# temp-battery-board.net
KiCad netlist of a schematic drawn in EAGLE
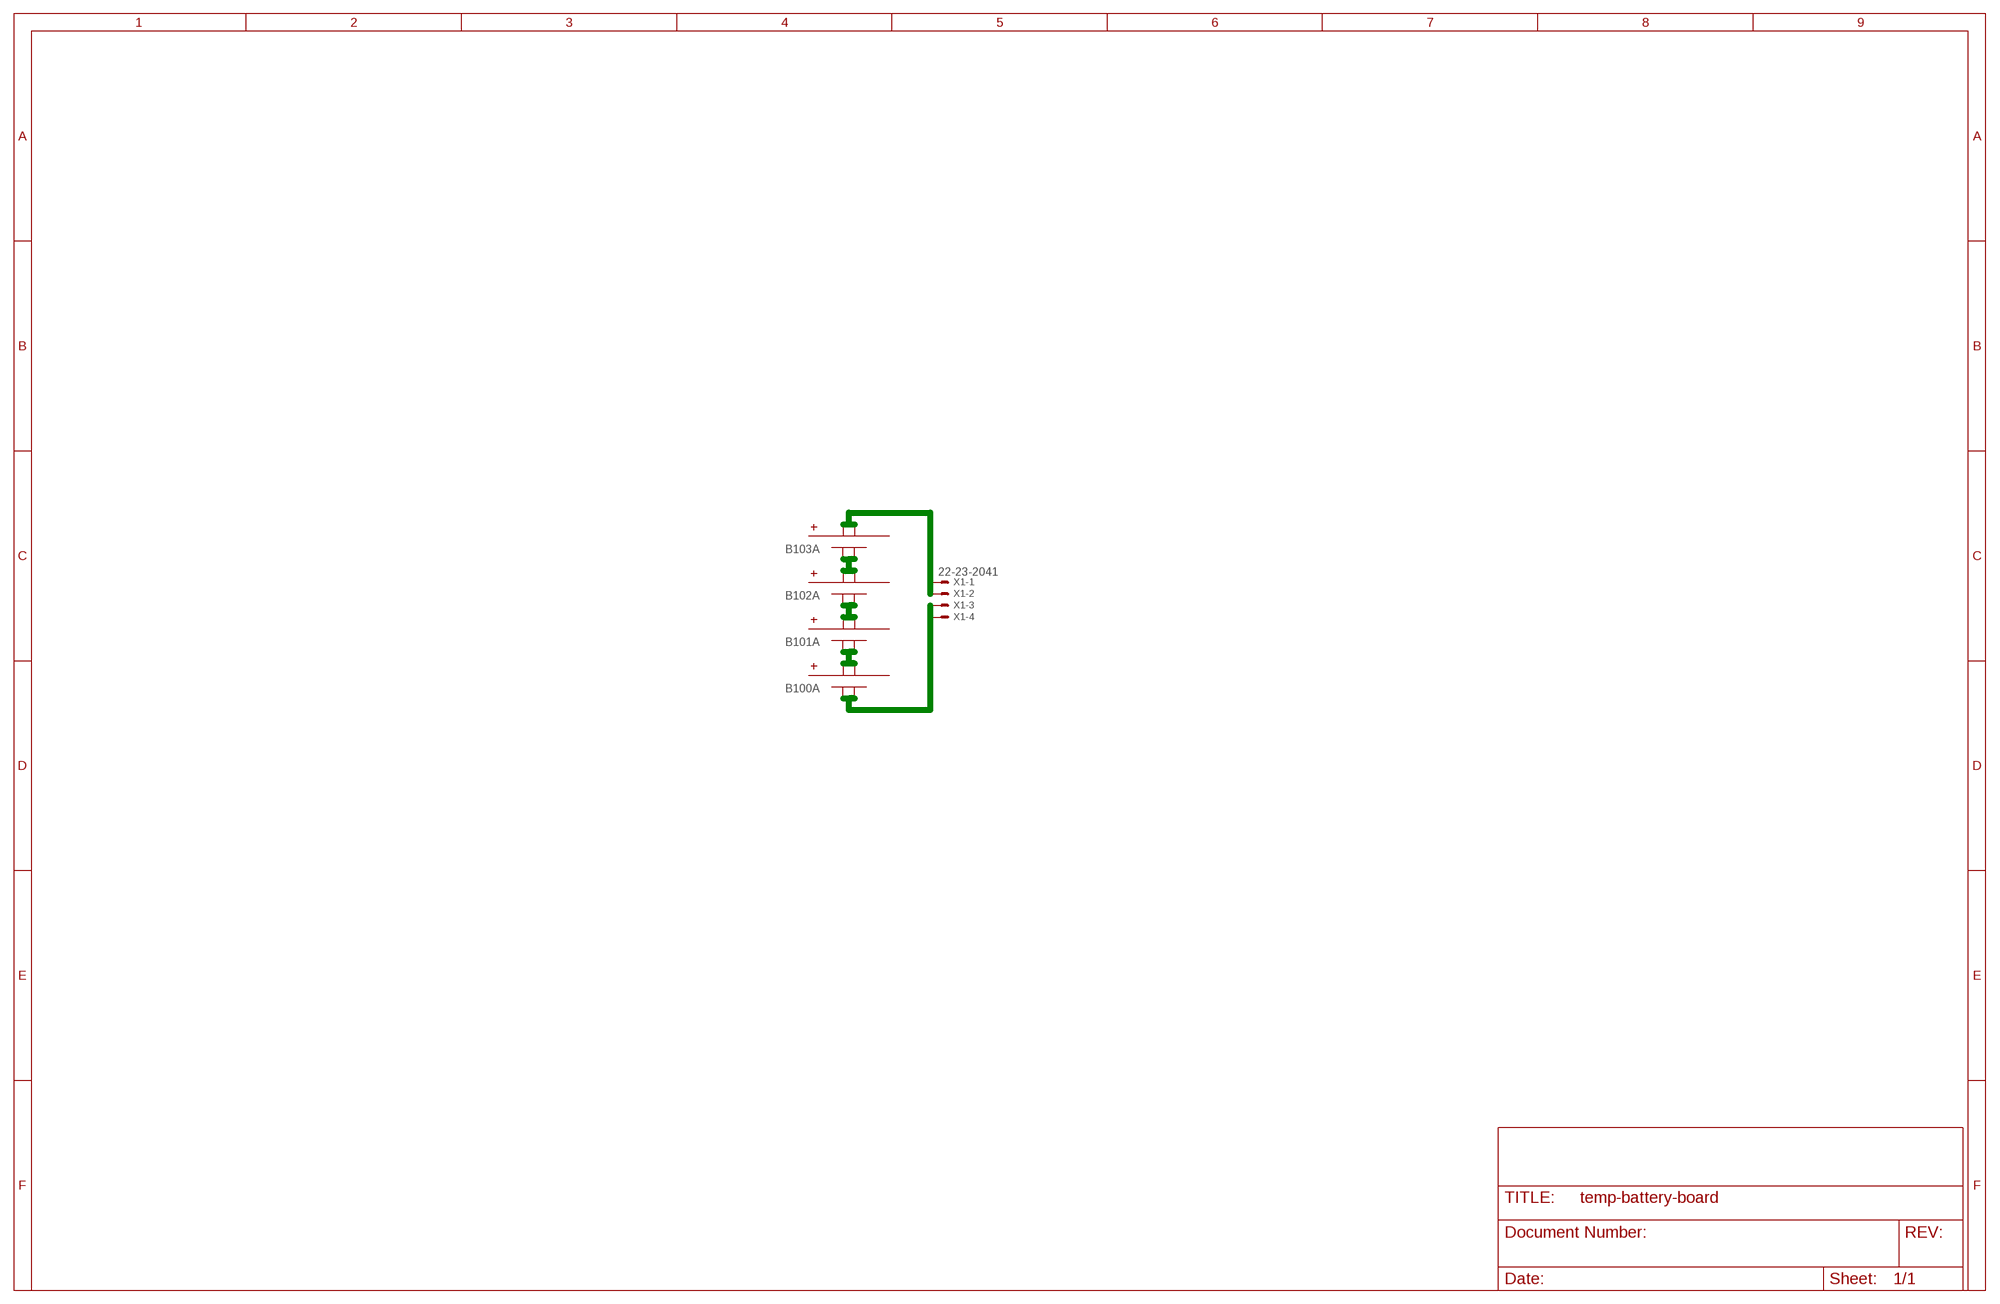
[diagram p0: schematic, sheet 1]

(export (version "E")
  (design (tool "Eeschema 10.0.6"))
  (components
    (comp (ref "B100A")
      (value "LIPO-8AHR")
      (footprint "eagle-import:LIPO-8AHR-PAC")
      (libsource (lib "eagle-import") (part "LIPO-8AHR"))
    )
    (comp (ref "B101A")
      (value "LIPO-8AHR")
      (footprint "eagle-import:LIPO-8AHR-PAC")
      (libsource (lib "eagle-import") (part "LIPO-8AHR"))
    )
    (comp (ref "B102A")
      (value "LIPO-8AHR")
      (footprint "eagle-import:LIPO-8AHR-PAC")
      (libsource (lib "eagle-import") (part "LIPO-8AHR"))
    )
    (comp (ref "B103A")
      (value "LIPO-8AHR")
      (footprint "eagle-import:LIPO-8AHR-PAC")
      (libsource (lib "eagle-import") (part "LIPO-8AHR"))
    )
    (comp (ref "X1")
      (value "22-23-2041")
      (footprint "eagle-import:22-23-2041")
      (libsource (lib "eagle-import") (part "22-23-2041"))
    )
  )
  (nets
    (net (code "1") (name "Net-(B100A-B+-PadB+@1)") (class "Default")
      (node (ref "B100A") (pin "B+@1") (pinfunction "B+_B+@1") (pintype "passive"))
      (node (ref "B100A") (pin "B+@2") (pinfunction "B+_B+@2") (pintype "passive"))
      (node (ref "B101A") (pin "B-@1") (pinfunction "B-_B-@1") (pintype "passive"))
      (node (ref "B101A") (pin "B-@2") (pinfunction "B-_B-@2") (pintype "passive"))
    )
    (net (code "2") (name "Net-(B101A-B+-PadB+@1)") (class "Default")
      (node (ref "B101A") (pin "B+@1") (pinfunction "B+_B+@1") (pintype "passive"))
      (node (ref "B101A") (pin "B+@2") (pinfunction "B+_B+@2") (pintype "passive"))
      (node (ref "B102A") (pin "B-@1") (pinfunction "B-_B-@1") (pintype "passive"))
      (node (ref "B102A") (pin "B-@2") (pinfunction "B-_B-@2") (pintype "passive"))
    )
    (net (code "3") (name "Net-(B102A-B+-PadB+@1)") (class "Default")
      (node (ref "B102A") (pin "B+@1") (pinfunction "B+_B+@1") (pintype "passive"))
      (node (ref "B102A") (pin "B+@2") (pinfunction "B+_B+@2") (pintype "passive"))
      (node (ref "B103A") (pin "B-@1") (pinfunction "B-_B-@1") (pintype "passive"))
      (node (ref "B103A") (pin "B-@2") (pinfunction "B-_B-@2") (pintype "passive"))
    )
    (net (code "4") (name "Net-(X1A-S)") (class "Default")
      (node (ref "B103A") (pin "B+@1") (pinfunction "B+_B+@1") (pintype "passive"))
      (node (ref "B103A") (pin "B+@2") (pinfunction "B+_B+@2") (pintype "passive"))
      (node (ref "X1") (pin "1") (pinfunction "S_1") (pintype "passive"))
      (node (ref "X1") (pin "2") (pinfunction "S_2") (pintype "passive"))
    )
    (net (code "5") (name "Net-(X1C-S)") (class "Default")
      (node (ref "B100A") (pin "B-@1") (pinfunction "B-_B-@1") (pintype "passive"))
      (node (ref "B100A") (pin "B-@2") (pinfunction "B-_B-@2") (pintype "passive"))
      (node (ref "X1") (pin "3") (pinfunction "S_3") (pintype "passive"))
      (node (ref "X1") (pin "4") (pinfunction "S_4") (pintype "passive"))
    )
  )
)
